# TinySmps.net
KiCad netlist of a schematic drawn in EAGLE
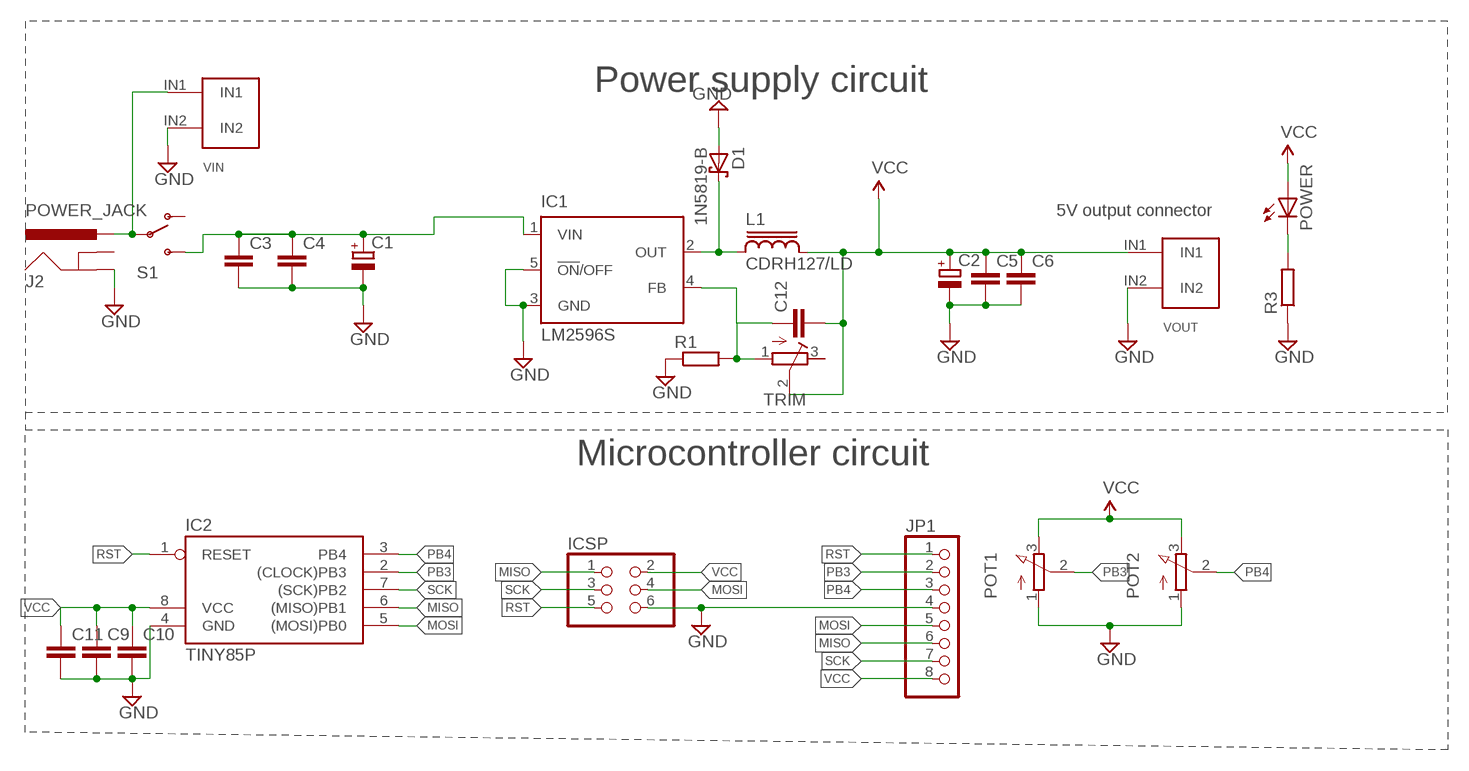
[diagram p0: schematic, sheet 1]

(export (version "E")
  (design (tool "Eeschema 10.0.6"))
  (components
    (comp (ref "C1")
      (value "CPOL-EUE7.5-16")
      (footprint "eagle-import:E7,5-16")
      (libsource (lib "eagle-import") (part "CPOL-EUE7.5-16"))
    )
    (comp (ref "C2")
      (value "CPOL-EUE5-10.5")
      (footprint "eagle-import:E5-10,5")
      (libsource (lib "eagle-import") (part "CPOL-EUE5-10.5"))
    )
    (comp (ref "C3")
      (value "C-EUC1206")
      (footprint "eagle-import:C1206")
      (libsource (lib "eagle-import") (part "C-EUC1206"))
    )
    (comp (ref "C4")
      (value "C-EUC1206")
      (footprint "eagle-import:C1206")
      (libsource (lib "eagle-import") (part "C-EUC1206"))
    )
    (comp (ref "C5")
      (value "C-EUC1206")
      (footprint "eagle-import:C1206")
      (libsource (lib "eagle-import") (part "C-EUC1206"))
    )
    (comp (ref "C6")
      (value "C-EUC1206")
      (footprint "eagle-import:C1206")
      (libsource (lib "eagle-import") (part "C-EUC1206"))
    )
    (comp (ref "C9")
      (value "C-EUC1206")
      (footprint "eagle-import:C1206")
      (libsource (lib "eagle-import") (part "C-EUC1206"))
    )
    (comp (ref "C10")
      (value "C-EUC1206")
      (footprint "eagle-import:C1206")
      (libsource (lib "eagle-import") (part "C-EUC1206"))
    )
    (comp (ref "C11")
      (value "C-EUC1206")
      (footprint "eagle-import:C1206")
      (libsource (lib "eagle-import") (part "C-EUC1206"))
    )
    (comp (ref "C12")
      (value "C2,5-3")
      (footprint "eagle-import:C2.5-3")
      (libsource (lib "eagle-import") (part "C2,5-3"))
    )
    (comp (ref "D1")
      (value "1N5819-B")
      (footprint "eagle-import:DO41-7.6")
      (libsource (lib "eagle-import") (part "1N5819-B"))
    )
    (comp (ref "IC1")
      (value "LM2596S")
      (footprint "eagle-import:TO263-5")
      (fields (field (name "MF") "NATIONAL SEMICONDUCTOR") (field (name "MPN") "LM2596S-ADJ/NOPB"))
      (libsource (lib "eagle-import") (part "LM2596S"))
    )
    (comp (ref "IC2")
      (value "TINY85P")
      (footprint "eagle-import:DIL08")
      (libsource (lib "eagle-import") (part "TINY22P"))
    )
    (comp (ref "ICSP")
      (value "PINHD-2X3")
      (footprint "eagle-import:2X03")
      (libsource (lib "eagle-import") (part "PINHD-2X3"))
    )
    (comp (ref "J2")
      (value "POWER_JACK")
      (footprint "eagle-import:POWER_JACK_PTH")
      (libsource (lib "eagle-import") (part "POWER_JACK"))
    )
    (comp (ref "JP1")
      (value "PINHD-1X8")
      (footprint "eagle-import:1X08")
      (libsource (lib "eagle-import") (part "PINHD-1X8"))
    )
    (comp (ref "L1")
      (value "CDRH127/LD")
      (footprint "eagle-import:CDRH127_LD")
      (libsource (lib "eagle-import") (part "CDRH127/LD"))
    )
    (comp (ref "POT1")
      (value "3RP/1610N")
      (footprint "eagle-import:3RP_1610N")
      (libsource (lib "eagle-import") (part "3RP/1610N"))
    )
    (comp (ref "POT2")
      (value "3RP/1610N")
      (footprint "eagle-import:3RP_1610N")
      (libsource (lib "eagle-import") (part "3RP/1610N"))
    )
    (comp (ref "POWER")
      (value "LEDSML0805")
      (footprint "eagle-import:SML0805")
      (libsource (lib "eagle-import") (part "LEDSML0805"))
    )
    (comp (ref "R1")
      (value "R-EU_0204/7")
      (footprint "eagle-import:0204_7")
      (libsource (lib "eagle-import") (part "R-EU_0204/7"))
    )
    (comp (ref "R3")
      (value "R-EU_R1206")
      (footprint "eagle-import:R1206")
      (libsource (lib "eagle-import") (part "resistor_R-EU_R1206"))
    )
    (comp (ref "S1")
      (value "SWITCH-SPDTKIT")
      (footprint "eagle-import:SWITCH-SPDT_KIT")
      (libsource (lib "eagle-import") (part "SWITCH-SPDTKIT"))
    )
    (comp (ref "TRIM")
      (value "R-TRIMM3296W")
      (footprint "eagle-import:RTRIM3296W")
      (libsource (lib "eagle-import") (part "R-TRIMM3296W"))
    )
    (comp (ref "VIN")
      (value "1X2_5MM")
      (footprint "eagle-import:1X2_5MM")
      (libsource (lib "eagle-import") (part "1X2_5MM"))
    )
    (comp (ref "VOUT")
      (value "1X2_5MM")
      (footprint "eagle-import:1X2_5MM")
      (libsource (lib "eagle-import") (part "1X2_5MM"))
    )
  )
  (nets
    (net (code "1") (name "GND") (class "Default")
      (node (ref "C1") (pin "-") (pinfunction "-_-") (pintype "passive"))
      (node (ref "C10") (pin "2") (pinfunction "2_2") (pintype "passive"))
      (node (ref "C11") (pin "2") (pinfunction "2_2") (pintype "passive"))
      (node (ref "C2") (pin "-") (pinfunction "-_-") (pintype "passive"))
      (node (ref "C3") (pin "2") (pinfunction "2_2") (pintype "passive"))
      (node (ref "C4") (pin "2") (pinfunction "2_2") (pintype "passive"))
      (node (ref "C5") (pin "2") (pinfunction "2_2") (pintype "passive"))
      (node (ref "C6") (pin "2") (pinfunction "2_2") (pintype "passive"))
      (node (ref "C9") (pin "2") (pinfunction "2_2") (pintype "passive"))
      (node (ref "D1") (pin "A") (pinfunction "A_A") (pintype "passive"))
      (node (ref "IC1") (pin "3") (pinfunction "GND_3") (pintype "power_in"))
      (node (ref "IC1") (pin "5") (pinfunction "~{ON}/OFF_5") (pintype "input"))
      (node (ref "IC2") (pin "4") (pinfunction "GND_4") (pintype "power_in"))
      (node (ref "ICSP") (pin "6") (pinfunction "6_6") (pintype "passive"))
      (node (ref "J2") (pin "GND") (pinfunction "GND_GND") (pintype "bidirectional"))
      (node (ref "JP1") (pin "4") (pinfunction "4_4") (pintype "passive"))
      (node (ref "POT1") (pin "1") (pinfunction "A_1") (pintype "passive"))
      (node (ref "POT2") (pin "1") (pinfunction "A_1") (pintype "passive"))
      (node (ref "R1") (pin "1") (pinfunction "1_1") (pintype "passive"))
      (node (ref "R3") (pin "1") (pinfunction "1_1") (pintype "passive"))
      (node (ref "VIN") (pin "IN2") (pinfunction "IN2_IN2") (pintype "bidirectional"))
      (node (ref "VOUT") (pin "IN2") (pinfunction "IN2_IN2") (pintype "bidirectional"))
    )
    (net (code "2") (name "MISO") (class "Default")
      (node (ref "IC2") (pin "6") (pinfunction "(MISO)PB1_6") (pintype "bidirectional"))
      (node (ref "ICSP") (pin "1") (pinfunction "1_1") (pintype "passive"))
      (node (ref "JP1") (pin "6") (pinfunction "6_6") (pintype "passive"))
    )
    (net (code "3") (name "MOSI") (class "Default")
      (node (ref "IC2") (pin "5") (pinfunction "(MOSI)PB0_5") (pintype "bidirectional"))
      (node (ref "ICSP") (pin "4") (pinfunction "4_4") (pintype "passive"))
      (node (ref "JP1") (pin "5") (pinfunction "5_5") (pintype "passive"))
    )
    (net (code "4") (name "Net-(IC1-FB)") (class "Default")
      (node (ref "C12") (pin "1") (pinfunction "1_1") (pintype "passive"))
      (node (ref "IC1") (pin "4") (pinfunction "FB_4") (pintype "input"))
      (node (ref "R1") (pin "2") (pinfunction "2_2") (pintype "passive"))
      (node (ref "TRIM") (pin "1") (pinfunction "A_1") (pintype "passive"))
    )
    (net (code "5") (name "Net-(IC1-OUT)") (class "Default")
      (node (ref "D1") (pin "C") (pinfunction "C_C") (pintype "passive"))
      (node (ref "IC1") (pin "2") (pinfunction "OUT_2") (pintype "output"))
      (node (ref "L1") (pin "1") (pinfunction "1_1") (pintype "passive"))
    )
    (net (code "6") (name "Net-(IC1-VIN)") (class "Default")
      (node (ref "C1") (pin "+") (pinfunction "+_+") (pintype "passive"))
      (node (ref "C3") (pin "1") (pinfunction "1_1") (pintype "passive"))
      (node (ref "C4") (pin "1") (pinfunction "1_1") (pintype "passive"))
      (node (ref "IC1") (pin "1") (pinfunction "VIN_1") (pintype "input"))
      (node (ref "S1") (pin "3") (pinfunction "S_3") (pintype "passive"))
    )
    (net (code "7") (name "Net-(POWER-PadC)") (class "Default")
      (node (ref "POWER") (pin "C") (pinfunction "C_C") (pintype "passive"))
      (node (ref "R3") (pin "2") (pinfunction "2_2") (pintype "passive"))
    )
    (net (code "8") (name "Net-(S1-P)") (class "Default")
      (node (ref "J2") (pin "PWR") (pinfunction "PWR_PWR") (pintype "bidirectional"))
      (node (ref "S1") (pin "2") (pinfunction "P_2") (pintype "passive"))
      (node (ref "VIN") (pin "IN1") (pinfunction "IN1_IN1") (pintype "bidirectional"))
    )
    (net (code "9") (name "PB3") (class "Default")
      (node (ref "IC2") (pin "2") (pinfunction "(CLOCK)PB3_2") (pintype "bidirectional"))
      (node (ref "JP1") (pin "2") (pinfunction "2_2") (pintype "passive"))
      (node (ref "POT1") (pin "2") (pinfunction "S_2") (pintype "passive"))
    )
    (net (code "10") (name "PB4") (class "Default")
      (node (ref "IC2") (pin "3") (pinfunction "PB4_3") (pintype "bidirectional"))
      (node (ref "JP1") (pin "3") (pinfunction "3_3") (pintype "passive"))
      (node (ref "POT2") (pin "2") (pinfunction "S_2") (pintype "passive"))
    )
    (net (code "11") (name "RST") (class "Default")
      (node (ref "IC2") (pin "1") (pinfunction "RESET_1") (pintype "input"))
      (node (ref "ICSP") (pin "5") (pinfunction "5_5") (pintype "passive"))
      (node (ref "JP1") (pin "1") (pinfunction "1_1") (pintype "passive"))
    )
    (net (code "12") (name "SCK") (class "Default")
      (node (ref "IC2") (pin "7") (pinfunction "(SCK)PB2_7") (pintype "bidirectional"))
      (node (ref "ICSP") (pin "3") (pinfunction "3_3") (pintype "passive"))
      (node (ref "JP1") (pin "7") (pinfunction "7_7") (pintype "passive"))
    )
    (net (code "13") (name "VCC") (class "Default")
      (node (ref "C10") (pin "1") (pinfunction "1_1") (pintype "passive"))
      (node (ref "C11") (pin "1") (pinfunction "1_1") (pintype "passive"))
      (node (ref "C12") (pin "2") (pinfunction "2_2") (pintype "passive"))
      (node (ref "C2") (pin "+") (pinfunction "+_+") (pintype "passive"))
      (node (ref "C5") (pin "1") (pinfunction "1_1") (pintype "passive"))
      (node (ref "C6") (pin "1") (pinfunction "1_1") (pintype "passive"))
      (node (ref "C9") (pin "1") (pinfunction "1_1") (pintype "passive"))
      (node (ref "IC2") (pin "8") (pinfunction "VCC_8") (pintype "power_in"))
      (node (ref "ICSP") (pin "2") (pinfunction "2_2") (pintype "passive"))
      (node (ref "JP1") (pin "8") (pinfunction "8_8") (pintype "passive"))
      (node (ref "L1") (pin "2") (pinfunction "2_2") (pintype "passive"))
      (node (ref "POT1") (pin "3") (pinfunction "E_3") (pintype "passive"))
      (node (ref "POT2") (pin "3") (pinfunction "E_3") (pintype "passive"))
      (node (ref "POWER") (pin "A") (pinfunction "A_A") (pintype "passive"))
      (node (ref "TRIM") (pin "2") (pinfunction "S_2") (pintype "passive"))
      (node (ref "VOUT") (pin "IN1") (pinfunction "IN1_IN1") (pintype "bidirectional"))
    )
    (net (code "14") (name "unconnected-(J2-PadGNDBREAK)") (class "Default")
      (node (ref "J2") (pin "GNDBREAK") (pinfunction "GNDBREAK_GNDBREAK") (pintype "bidirectional"))
    )
    (net (code "15") (name "unconnected-(S1-O-Pad1)") (class "Default")
      (node (ref "S1") (pin "1") (pinfunction "O_1") (pintype "passive"))
    )
    (net (code "16") (name "unconnected-(TRIM-E-Pad3)") (class "Default")
      (node (ref "TRIM") (pin "3") (pinfunction "E_3") (pintype "passive"))
    )
  )
)
